# deskav2.net
KiCad netlist of a schematic drawn in EAGLE
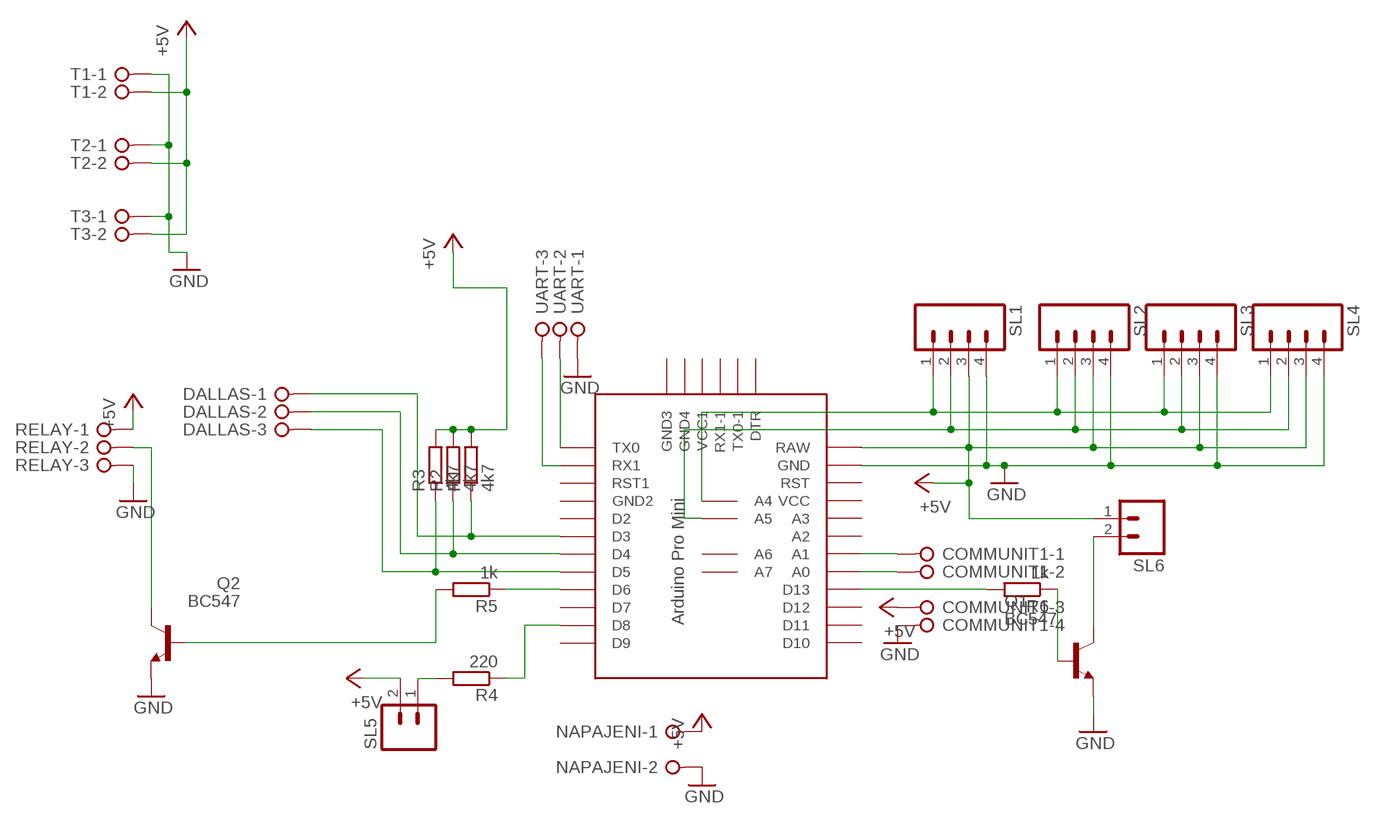
[diagram p0: schematic, sheet 1]

(export (version "E")
  (design (tool "Eeschema 10.0.6"))
  (components
    (comp (ref "COMMUNIT1")
      (value "W237-04P")
      (footprint "eagle-import:W237-4P")
      (libsource (lib "eagle-import") (part "W237-04P"))
    )
    (comp (ref "DALLAS")
      (value "W237-3E")
      (footprint "eagle-import:W237-3E")
      (libsource (lib "eagle-import") (part "W237-3E"))
    )
    (comp (ref "NAPAJENI")
      (value "W237-02P")
      (footprint "eagle-import:W237-132")
      (libsource (lib "eagle-import") (part "W237-02P"))
    )
    (comp (ref "Q1")
      (value "BC547")
      (footprint "eagle-import:TO92")
      (libsource (lib "eagle-import") (part "BC547"))
    )
    (comp (ref "Q2")
      (value "BC547")
      (footprint "eagle-import:TO92")
      (libsource (lib "eagle-import") (part "BC547"))
    )
    (comp (ref "R1")
      (value "4k7")
      (footprint "eagle-import:0207_7")
      (libsource (lib "eagle-import") (part "R-EU_0207/7"))
    )
    (comp (ref "R2")
      (value "4k7")
      (footprint "eagle-import:0207_7")
      (libsource (lib "eagle-import") (part "R-EU_0207/7"))
    )
    (comp (ref "R3")
      (value "4k7")
      (footprint "eagle-import:0207_7")
      (libsource (lib "eagle-import") (part "R-EU_0207/7"))
    )
    (comp (ref "R4")
      (value "220")
      (footprint "eagle-import:0207_7")
      (libsource (lib "eagle-import") (part "R-EU_0207/7"))
    )
    (comp (ref "R5")
      (value "1k")
      (footprint "eagle-import:0207_7")
      (libsource (lib "eagle-import") (part "R-EU_0207/7"))
    )
    (comp (ref "R6")
      (value "1k")
      (footprint "eagle-import:0207_7")
      (libsource (lib "eagle-import") (part "R-EU_0207/7"))
    )
    (comp (ref "RELAY")
      (value "W237-3E")
      (footprint "eagle-import:W237-3E")
      (libsource (lib "eagle-import") (part "W237-3E"))
    )
    (comp (ref "SL1")
      (value "M04")
      (footprint "eagle-import:04P")
      (libsource (lib "eagle-import") (part "M04"))
    )
    (comp (ref "SL2")
      (value "M04")
      (footprint "eagle-import:04P")
      (libsource (lib "eagle-import") (part "M04"))
    )
    (comp (ref "SL3")
      (value "M04")
      (footprint "eagle-import:04P")
      (libsource (lib "eagle-import") (part "M04"))
    )
    (comp (ref "SL4")
      (value "M04")
      (footprint "eagle-import:04P")
      (libsource (lib "eagle-import") (part "M04"))
    )
    (comp (ref "SL5")
      (value "M02")
      (footprint "eagle-import:02P")
      (libsource (lib "eagle-import") (part "M02"))
    )
    (comp (ref "SL6")
      (value "M02")
      (footprint "eagle-import:02P")
      (libsource (lib "eagle-import") (part "M02"))
    )
    (comp (ref "T1")
      (value "W237-02P")
      (footprint "eagle-import:W237-132")
      (libsource (lib "eagle-import") (part "W237-02P"))
    )
    (comp (ref "T2")
      (value "W237-02P")
      (footprint "eagle-import:W237-132")
      (libsource (lib "eagle-import") (part "W237-02P"))
    )
    (comp (ref "T3")
      (value "W237-02P")
      (footprint "eagle-import:W237-132")
      (libsource (lib "eagle-import") (part "W237-02P"))
    )
    (comp (ref "U$1")
      (value "PRO-MINI-2")
      (footprint "eagle-import:PRO-MINI-2")
      (libsource (lib "eagle-import") (part "PRO-MINI-2"))
    )
    (comp (ref "UART")
      (value "W237-3E")
      (footprint "eagle-import:W237-3E")
      (libsource (lib "eagle-import") (part "W237-3E"))
    )
  )
  (nets
    (net (code "1") (name "+5V") (class "Default")
      (node (ref "COMMUNIT1") (pin "3") (pinfunction "KL_3") (pintype "passive"))
      (node (ref "NAPAJENI") (pin "1") (pinfunction "KL_1") (pintype "passive"))
      (node (ref "R1") (pin "2") (pinfunction "2_2") (pintype "passive"))
      (node (ref "R2") (pin "2") (pinfunction "2_2") (pintype "passive"))
      (node (ref "R3") (pin "2") (pinfunction "2_2") (pintype "passive"))
      (node (ref "RELAY") (pin "1") (pinfunction "KL_1") (pintype "passive"))
      (node (ref "SL1") (pin "3") (pinfunction "3_3") (pintype "passive"))
      (node (ref "SL2") (pin "3") (pinfunction "3_3") (pintype "passive"))
      (node (ref "SL3") (pin "3") (pinfunction "3_3") (pintype "passive"))
      (node (ref "SL4") (pin "3") (pinfunction "3_3") (pintype "passive"))
      (node (ref "SL5") (pin "2") (pinfunction "2_2") (pintype "passive"))
      (node (ref "SL6") (pin "1") (pinfunction "1_1") (pintype "passive"))
      (node (ref "T1") (pin "2") (pinfunction "KL_2") (pintype "passive"))
      (node (ref "T2") (pin "2") (pinfunction "KL_2") (pintype "passive"))
      (node (ref "T3") (pin "2") (pinfunction "KL_2") (pintype "passive"))
      (node (ref "U$1") (pin "RAW") (pinfunction "RAW_RAW") (pintype "bidirectional"))
    )
    (net (code "2") (name "GND") (class "Default")
      (node (ref "COMMUNIT1") (pin "4") (pinfunction "KL_4") (pintype "passive"))
      (node (ref "NAPAJENI") (pin "2") (pinfunction "KL_2") (pintype "passive"))
      (node (ref "Q1") (pin "1") (pinfunction "E_1") (pintype "passive"))
      (node (ref "Q2") (pin "1") (pinfunction "E_1") (pintype "passive"))
      (node (ref "RELAY") (pin "3") (pinfunction "KL_3") (pintype "passive"))
      (node (ref "SL1") (pin "4") (pinfunction "4_4") (pintype "passive"))
      (node (ref "SL2") (pin "4") (pinfunction "4_4") (pintype "passive"))
      (node (ref "SL3") (pin "4") (pinfunction "4_4") (pintype "passive"))
      (node (ref "SL4") (pin "4") (pinfunction "4_4") (pintype "passive"))
      (node (ref "T1") (pin "1") (pinfunction "KL_1") (pintype "passive"))
      (node (ref "T2") (pin "1") (pinfunction "KL_1") (pintype "passive"))
      (node (ref "T3") (pin "1") (pinfunction "KL_1") (pintype "passive"))
      (node (ref "U$1") (pin "GND") (pinfunction "GND_GND") (pintype "bidirectional"))
      (node (ref "UART") (pin "1") (pinfunction "KL_1") (pintype "passive"))
    )
    (net (code "3") (name "Net-(COMMUNIT1A-KL)") (class "Default")
      (node (ref "COMMUNIT1") (pin "1") (pinfunction "KL_1") (pintype "passive"))
      (node (ref "U$1") (pin "A1") (pinfunction "A1_A1") (pintype "bidirectional"))
    )
    (net (code "4") (name "Net-(COMMUNIT1B-KL)") (class "Default")
      (node (ref "COMMUNIT1") (pin "2") (pinfunction "KL_2") (pintype "passive"))
      (node (ref "U$1") (pin "A0") (pinfunction "A0_A0") (pintype "bidirectional"))
    )
    (net (code "5") (name "Net-(DALLASA-KL)") (class "Default")
      (node (ref "DALLAS") (pin "1") (pinfunction "KL_1") (pintype "passive"))
      (node (ref "R1") (pin "1") (pinfunction "1_1") (pintype "passive"))
      (node (ref "U$1") (pin "D3") (pinfunction "D3_D3") (pintype "bidirectional"))
    )
    (net (code "6") (name "Net-(DALLASB-KL)") (class "Default")
      (node (ref "DALLAS") (pin "2") (pinfunction "KL_2") (pintype "passive"))
      (node (ref "R2") (pin "1") (pinfunction "1_1") (pintype "passive"))
      (node (ref "U$1") (pin "D4") (pinfunction "D4_D4") (pintype "bidirectional"))
    )
    (net (code "7") (name "Net-(DALLASC-KL)") (class "Default")
      (node (ref "DALLAS") (pin "3") (pinfunction "KL_3") (pintype "passive"))
      (node (ref "R3") (pin "1") (pinfunction "1_1") (pintype "passive"))
      (node (ref "U$1") (pin "D5") (pinfunction "D5_D5") (pintype "bidirectional"))
    )
    (net (code "8") (name "Net-(Q1-B)") (class "Default")
      (node (ref "Q1") (pin "2") (pinfunction "B_2") (pintype "passive"))
      (node (ref "R6") (pin "1") (pinfunction "1_1") (pintype "passive"))
    )
    (net (code "9") (name "Net-(Q1-C)") (class "Default")
      (node (ref "Q1") (pin "3") (pinfunction "C_3") (pintype "passive"))
      (node (ref "SL6") (pin "2") (pinfunction "2_2") (pintype "passive"))
    )
    (net (code "10") (name "Net-(Q2-B)") (class "Default")
      (node (ref "Q2") (pin "2") (pinfunction "B_2") (pintype "passive"))
      (node (ref "R5") (pin "2") (pinfunction "2_2") (pintype "passive"))
    )
    (net (code "11") (name "Net-(Q2-C)") (class "Default")
      (node (ref "Q2") (pin "3") (pinfunction "C_3") (pintype "passive"))
      (node (ref "RELAY") (pin "2") (pinfunction "KL_2") (pintype "passive"))
    )
    (net (code "12") (name "Net-(R4-Pad1)") (class "Default")
      (node (ref "R4") (pin "1") (pinfunction "1_1") (pintype "passive"))
      (node (ref "U$1") (pin "D8") (pinfunction "D8_D8") (pintype "bidirectional"))
    )
    (net (code "13") (name "Net-(R4-Pad2)") (class "Default")
      (node (ref "R4") (pin "2") (pinfunction "2_2") (pintype "passive"))
      (node (ref "SL5") (pin "1") (pinfunction "1_1") (pintype "passive"))
    )
    (net (code "14") (name "Net-(R5-Pad1)") (class "Default")
      (node (ref "R5") (pin "1") (pinfunction "1_1") (pintype "passive"))
      (node (ref "U$1") (pin "D6") (pinfunction "D6_D6") (pintype "bidirectional"))
    )
    (net (code "15") (name "Net-(R6-Pad2)") (class "Default")
      (node (ref "R6") (pin "2") (pinfunction "2_2") (pintype "passive"))
      (node (ref "U$1") (pin "D13") (pinfunction "D13_D13") (pintype "bidirectional"))
    )
    (net (code "16") (name "Net-(SL1-Pad1)") (class "Default")
      (node (ref "SL1") (pin "1") (pinfunction "1_1") (pintype "passive"))
      (node (ref "SL2") (pin "1") (pinfunction "1_1") (pintype "passive"))
      (node (ref "SL3") (pin "1") (pinfunction "1_1") (pintype "passive"))
      (node (ref "SL4") (pin "1") (pinfunction "1_1") (pintype "passive"))
      (node (ref "U$1") (pin "A4") (pinfunction "A4_A4") (pintype "bidirectional"))
    )
    (net (code "17") (name "Net-(SL1-Pad2)") (class "Default")
      (node (ref "SL1") (pin "2") (pinfunction "2_2") (pintype "passive"))
      (node (ref "SL2") (pin "2") (pinfunction "2_2") (pintype "passive"))
      (node (ref "SL3") (pin "2") (pinfunction "2_2") (pintype "passive"))
      (node (ref "SL4") (pin "2") (pinfunction "2_2") (pintype "passive"))
      (node (ref "U$1") (pin "A5") (pinfunction "A5_A5") (pintype "bidirectional"))
    )
    (net (code "18") (name "Net-(UARTB-KL)") (class "Default")
      (node (ref "U$1") (pin "TX0") (pinfunction "TX0_TX0") (pintype "bidirectional"))
      (node (ref "UART") (pin "2") (pinfunction "KL_2") (pintype "passive"))
    )
    (net (code "19") (name "Net-(UARTC-KL)") (class "Default")
      (node (ref "U$1") (pin "RX1") (pinfunction "RX1_RX1") (pintype "bidirectional"))
      (node (ref "UART") (pin "3") (pinfunction "KL_3") (pintype "passive"))
    )
    (net (code "20") (name "unconnected-(U$1-GND2-PadGND1)") (class "Default")
      (node (ref "U$1") (pin "GND1") (pinfunction "GND2_GND1") (pintype "bidirectional"))
    )
    (net (code "21") (name "unconnected-(U$1-GND3-PadGND2)") (class "Default")
      (node (ref "U$1") (pin "GND2") (pinfunction "GND3_GND2") (pintype "bidirectional"))
    )
    (net (code "22") (name "unconnected-(U$1-GND4-PadGND3)") (class "Default")
      (node (ref "U$1") (pin "GND3") (pinfunction "GND4_GND3") (pintype "bidirectional"))
    )
    (net (code "23") (name "unconnected-(U$1-PadA2)") (class "Default")
      (node (ref "U$1") (pin "A2") (pinfunction "A2_A2") (pintype "bidirectional"))
    )
    (net (code "24") (name "unconnected-(U$1-PadA3)") (class "Default")
      (node (ref "U$1") (pin "A3") (pinfunction "A3_A3") (pintype "bidirectional"))
    )
    (net (code "25") (name "unconnected-(U$1-PadA6)") (class "Default")
      (node (ref "U$1") (pin "A6") (pinfunction "A6_A6") (pintype "bidirectional"))
    )
    (net (code "26") (name "unconnected-(U$1-PadA7)") (class "Default")
      (node (ref "U$1") (pin "A7") (pinfunction "A7_A7") (pintype "bidirectional"))
    )
    (net (code "27") (name "unconnected-(U$1-PadD2)") (class "Default")
      (node (ref "U$1") (pin "D2") (pinfunction "D2_D2") (pintype "bidirectional"))
    )
    (net (code "28") (name "unconnected-(U$1-PadD7)") (class "Default")
      (node (ref "U$1") (pin "D7") (pinfunction "D7_D7") (pintype "bidirectional"))
    )
    (net (code "29") (name "unconnected-(U$1-PadD9)") (class "Default")
      (node (ref "U$1") (pin "D9") (pinfunction "D9_D9") (pintype "bidirectional"))
    )
    (net (code "30") (name "unconnected-(U$1-PadD10)") (class "Default")
      (node (ref "U$1") (pin "D10") (pinfunction "D10_D10") (pintype "bidirectional"))
    )
    (net (code "31") (name "unconnected-(U$1-PadD11)") (class "Default")
      (node (ref "U$1") (pin "D11") (pinfunction "D11_D11") (pintype "bidirectional"))
    )
    (net (code "32") (name "unconnected-(U$1-PadD12)") (class "Default")
      (node (ref "U$1") (pin "D12") (pinfunction "D12_D12") (pintype "bidirectional"))
    )
    (net (code "33") (name "unconnected-(U$1-PadDTR)") (class "Default")
      (node (ref "U$1") (pin "DTR") (pinfunction "DTR_DTR") (pintype "bidirectional"))
    )
    (net (code "34") (name "unconnected-(U$1-PadRST)") (class "Default")
      (node (ref "U$1") (pin "RST") (pinfunction "RST_RST") (pintype "bidirectional"))
    )
    (net (code "35") (name "unconnected-(U$1-PadRST1)") (class "Default")
      (node (ref "U$1") (pin "RST1") (pinfunction "RST1_RST1") (pintype "bidirectional"))
    )
    (net (code "36") (name "unconnected-(U$1-PadRX1-1)") (class "Default")
      (node (ref "U$1") (pin "RX1-1") (pinfunction "RX1-1_RX1-1") (pintype "bidirectional"))
    )
    (net (code "37") (name "unconnected-(U$1-PadTX0-1)") (class "Default")
      (node (ref "U$1") (pin "TX0-1") (pinfunction "TX0-1_TX0-1") (pintype "bidirectional"))
    )
    (net (code "38") (name "unconnected-(U$1-PadVCC)") (class "Default")
      (node (ref "U$1") (pin "VCC") (pinfunction "VCC_VCC") (pintype "bidirectional"))
    )
    (net (code "39") (name "unconnected-(U$1-PadVCC1)") (class "Default")
      (node (ref "U$1") (pin "VCC1") (pinfunction "VCC1_VCC1") (pintype "bidirectional"))
    )
  )
)
